# Safety_Loops.net
KiCad netlist of a schematic drawn in Altium Designer
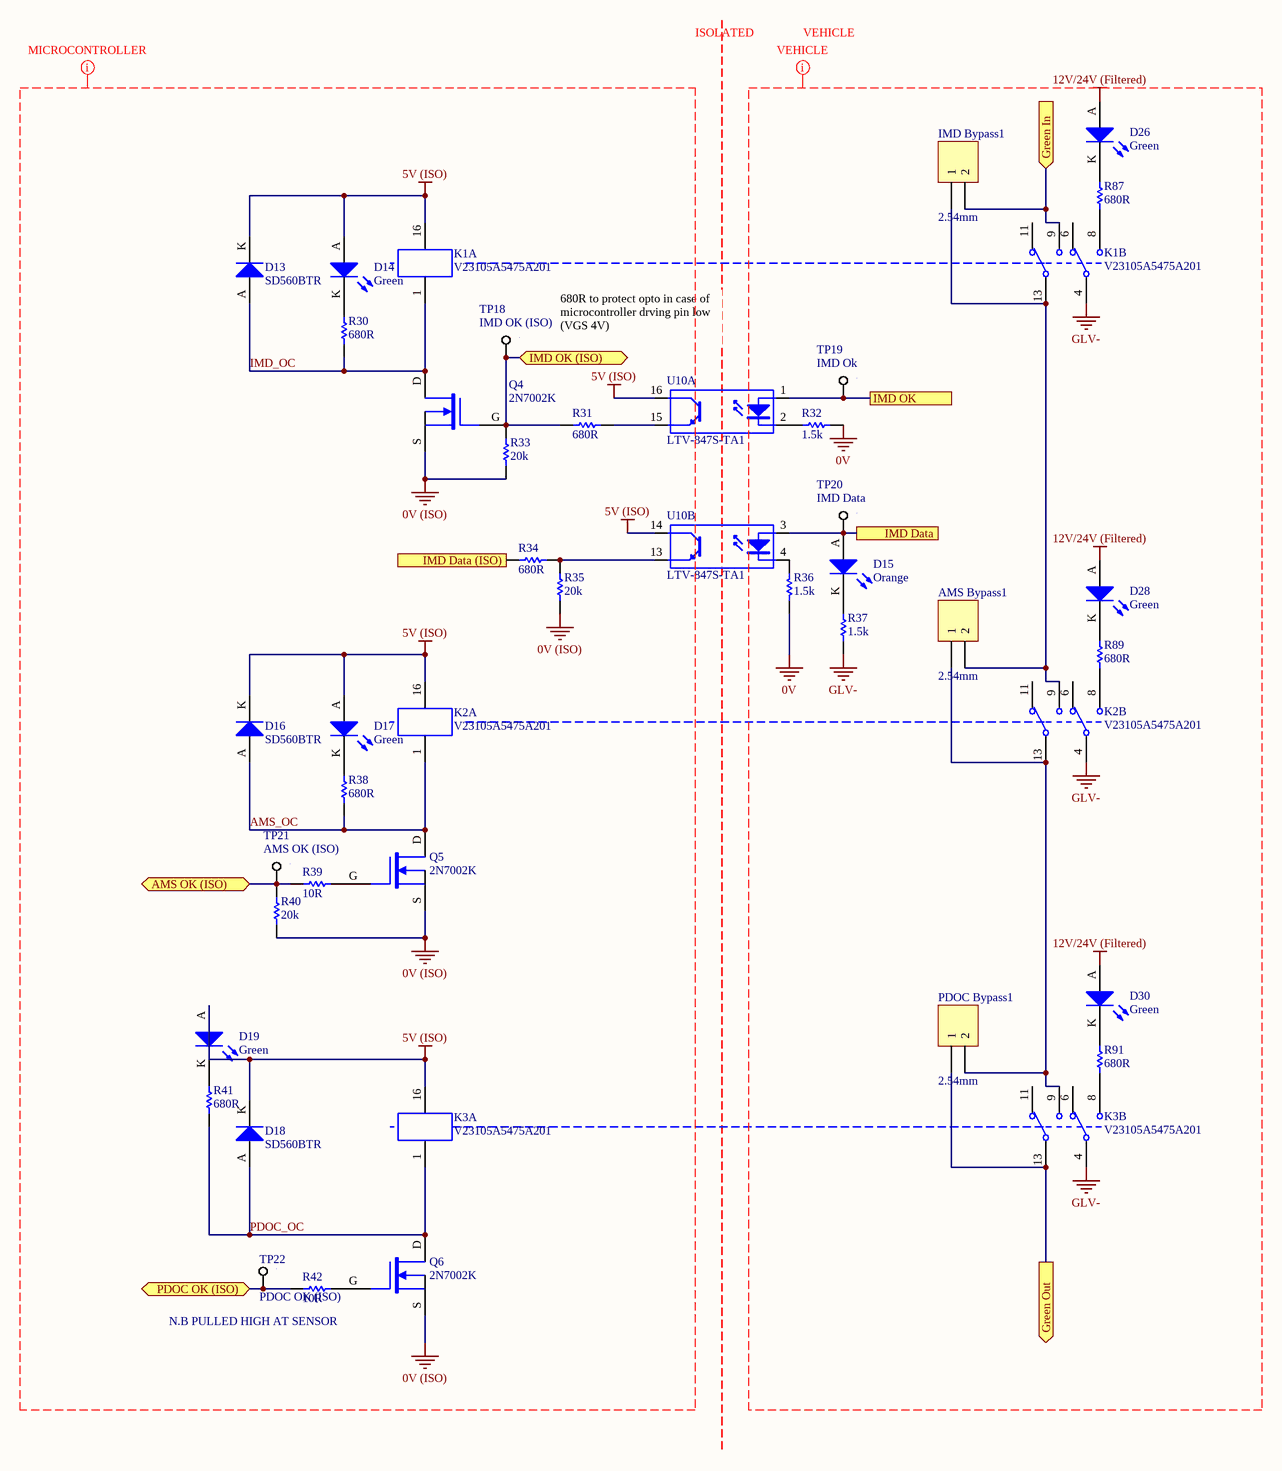
[diagram p0: Safety Loops.SchDoc]

(export (version "E")
  (design (tool "Eeschema 10.0.6"))
  (components
    (comp (ref "AMS Bypass1")
      (value "2.54mm")
      (footprint "TH 2.54mm Header 1x2")
      (fields (field (name "PART NUMBER") "TH 2.54mm Header 1x2") (field (name "CONTACT") "NA"))
      (libsource (lib "ts_20-standard-connectors") (part "Header 1x2"))
    )
    (comp (ref "D13")
      (value "SD560BTR")
      (footprint "SMB Diode")
      (description "1.2V_F 600V 5A SMB")
      (fields
        (field (name "MANUFACTURER") "SMC Diode Solutions")
        (field (name "DIGIKEY PART NUMBER") "1655-1530-2-ND")
      )
      (libsource (lib "ts_20-standard-library") (part "Diode"))
    )
    (comp (ref "D14")
      (value "Green")
      (footprint "0805 LED")
      (description "Green LED Indication - Discrete 1.75V 0805 (2012 Metric)")
      (fields (field (name "PART NUMBER") "SML-210FTT86") (field (name "MANUFACTURER") "ROHM Semiconductor"))
      (libsource (lib "ts_20-standard-library") (part "LED"))
    )
    (comp (ref "D15")
      (value "Orange")
      (footprint "0805 LED")
      (description "Orange LED Indication - Discrete 1.75V 0805 (2012 Metric)")
      (fields (field (name "PART NUMBER") "SML-211DTT86") (field (name "MANUFACTURER") "ROHM Semiconductor"))
      (libsource (lib "ts_20-standard-library") (part "LED"))
    )
    (comp (ref "D16")
      (value "SD560BTR")
      (footprint "SMB Diode")
      (description "1.2V_F 600V 5A SMB")
      (fields
        (field (name "MANUFACTURER") "SMC Diode Solutions")
        (field (name "DIGIKEY PART NUMBER") "1655-1530-2-ND")
      )
      (libsource (lib "ts_20-standard-library") (part "Diode"))
    )
    (comp (ref "D17")
      (value "Green")
      (footprint "0805 LED")
      (description "Green LED Indication - Discrete 1.75V 0805 (2012 Metric)")
      (fields (field (name "PART NUMBER") "SML-210FTT86") (field (name "MANUFACTURER") "ROHM Semiconductor"))
      (libsource (lib "ts_20-standard-library") (part "LED"))
    )
    (comp (ref "D18")
      (value "SD560BTR")
      (footprint "SMB Diode")
      (description "1.2V_F 600V 5A SMB")
      (fields
        (field (name "MANUFACTURER") "SMC Diode Solutions")
        (field (name "DIGIKEY PART NUMBER") "1655-1530-2-ND")
      )
      (libsource (lib "ts_20-standard-library") (part "Diode"))
    )
    (comp (ref "D19")
      (value "Green")
      (footprint "0805 LED")
      (description "Green LED Indication - Discrete 1.75V 0805 (2012 Metric)")
      (fields (field (name "PART NUMBER") "SML-210FTT86") (field (name "MANUFACTURER") "ROHM Semiconductor"))
      (libsource (lib "ts_20-standard-library") (part "LED"))
    )
    (comp (ref "D26")
      (value "Green")
      (footprint "0805 LED")
      (description "Green LED Indication - Discrete 1.75V 0805 (2012 Metric)")
      (fields (field (name "PART NUMBER") "SML-210FTT86") (field (name "MANUFACTURER") "ROHM Semiconductor"))
      (libsource (lib "ts_20-standard-library") (part "LED"))
    )
    (comp (ref "D28")
      (value "Green")
      (footprint "0805 LED")
      (description "Green LED Indication - Discrete 1.75V 0805 (2012 Metric)")
      (fields (field (name "PART NUMBER") "SML-210FTT86") (field (name "MANUFACTURER") "ROHM Semiconductor"))
      (libsource (lib "ts_20-standard-library") (part "LED"))
    )
    (comp (ref "D30")
      (value "Green")
      (footprint "0805 LED")
      (description "Green LED Indication - Discrete 1.75V 0805 (2012 Metric)")
      (fields (field (name "PART NUMBER") "SML-210FTT86") (field (name "MANUFACTURER") "ROHM Semiconductor"))
      (libsource (lib "ts_20-standard-library") (part "LED"))
    )
    (comp (ref "IMD Bypass1")
      (value "2.54mm")
      (footprint "TH 2.54mm Header 1x2")
      (fields (field (name "PART NUMBER") "TH 2.54mm Header 1x2") (field (name "CONTACT") "NA"))
      (libsource (lib "ts_20-standard-connectors") (part "Header 1x2"))
    )
    (comp (ref "K1")
      (value "V23105A5475A201")
      (footprint "TI 2-DIL")
      (description "5V DPDT Relay 3A 220VDC")
      (fields (field (name "MANUFACTURER") "Axicom") (field (name "DIGIKEY PART NUMBER") "PB383-ND"))
      (libsource (lib "") (part "V23105A5475A201_1"))
    )
    (comp (ref "K2")
      (value "V23105A5475A201")
      (footprint "TI 2-DIL")
      (description "5V DPDT Relay 3A 220VDC")
      (fields (field (name "MANUFACTURER") "Axicom") (field (name "DIGIKEY PART NUMBER") "PB383-ND"))
      (libsource (lib "") (part "V23105A5475A201_1"))
    )
    (comp (ref "K3")
      (value "V23105A5475A201")
      (footprint "TI 2-DIL")
      (description "5V DPDT Relay 3A 220VDC")
      (fields (field (name "MANUFACTURER") "Axicom") (field (name "DIGIKEY PART NUMBER") "PB383-ND"))
      (libsource (lib "") (part "V23105A5475A201_1"))
    )
    (comp (ref "PDOC Bypass1")
      (value "2.54mm")
      (footprint "TH 2.54mm Header 1x2")
      (fields (field (name "PART NUMBER") "TH 2.54mm Header 1x2") (field (name "CONTACT") "NA"))
      (libsource (lib "ts_20-standard-connectors") (part "Header 1x2"))
    )
    (comp (ref "Q4")
      (value "2N7002K")
      (footprint "ON SOT-23 MOSFET")
      (description "60V 380mA, NFET MOSTFET (Small Signal)")
      (fields
        (field (name "MANUFACTURER") "ON Semiconductor")
        (field (name "DIGIKEY PART NUMBER") "2N7002KCT-ND")
        (field (name "PUBLISHER") "Altium Limited")
      )
      (libsource (lib "ts_20-standard-library") (part "MOSFET-N"))
    )
    (comp (ref "Q5")
      (value "2N7002K")
      (footprint "ON SOT-23 MOSFET")
      (description "60V 380mA, NFET MOSTFET (Small Signal)")
      (fields
        (field (name "MANUFACTURER") "ON Semiconductor")
        (field (name "DIGIKEY PART NUMBER") "2N7002KCT-ND")
        (field (name "PUBLISHER") "Altium Limited")
      )
      (libsource (lib "ts_20-standard-library") (part "MOSFET-N"))
    )
    (comp (ref "Q6")
      (value "2N7002K")
      (footprint "ON SOT-23 MOSFET")
      (description "60V 380mA, NFET MOSTFET (Small Signal)")
      (fields
        (field (name "MANUFACTURER") "ON Semiconductor")
        (field (name "DIGIKEY PART NUMBER") "2N7002KCT-ND")
        (field (name "PUBLISHER") "Altium Limited")
      )
      (libsource (lib "ts_20-standard-library") (part "MOSFET-N"))
    )
    (comp (ref "R30")
      (value "680R")
      (footprint "0805")
      (fields
        (field (name "PART NUMBER") "RC0805FR07680RL")
        (field (name "MANUFACTURER") "YAGEO")
        (field (name "TOLERANCE") "0.01")
      )
      (libsource (lib "ts_20-standard-library") (part "Resistor"))
    )
    (comp (ref "R31")
      (value "680R")
      (footprint "0805")
      (fields
        (field (name "PART NUMBER") "RC0805FR07680RL")
        (field (name "MANUFACTURER") "YAGEO")
        (field (name "TOLERANCE") "0.01")
      )
      (libsource (lib "ts_20-standard-library") (part "Resistor"))
    )
    (comp (ref "R32")
      (value "1.5k")
      (footprint "0805")
      (fields
        (field (name "PART NUMBER") "RC0805FR071K5L")
        (field (name "MANUFACTURER") "YAGEO")
        (field (name "TOLERANCE") "0.01")
      )
      (libsource (lib "ts_20-standard-library") (part "Resistor"))
    )
    (comp (ref "R33")
      (value "20k")
      (footprint "0805")
      (fields
        (field (name "PART NUMBER") "RC0805FR0720KL")
        (field (name "MANUFACTURER") "YAGEO")
        (field (name "TOLERANCE") "0.01")
      )
      (libsource (lib "ts_20-standard-library") (part "Resistor"))
    )
    (comp (ref "R34")
      (value "680R")
      (footprint "0805")
      (fields
        (field (name "PART NUMBER") "RC0805FR07680RL")
        (field (name "MANUFACTURER") "YAGEO")
        (field (name "TOLERANCE") "0.01")
      )
      (libsource (lib "ts_20-standard-library") (part "Resistor"))
    )
    (comp (ref "R35")
      (value "20k")
      (footprint "0805")
      (fields
        (field (name "PART NUMBER") "RC0805FR0720KL")
        (field (name "MANUFACTURER") "YAGEO")
        (field (name "TOLERANCE") "0.01")
      )
      (libsource (lib "ts_20-standard-library") (part "Resistor"))
    )
    (comp (ref "R36")
      (value "1.5k")
      (footprint "0805")
      (fields
        (field (name "PART NUMBER") "RC0805FR071K5L")
        (field (name "MANUFACTURER") "YAGEO")
        (field (name "TOLERANCE") "0.01")
      )
      (libsource (lib "ts_20-standard-library") (part "Resistor"))
    )
    (comp (ref "R37")
      (value "1.5k")
      (footprint "0805")
      (fields
        (field (name "PART NUMBER") "RC0805FR071K5L")
        (field (name "MANUFACTURER") "YAGEO")
        (field (name "TOLERANCE") "0.01")
      )
      (libsource (lib "ts_20-standard-library") (part "Resistor"))
    )
    (comp (ref "R38")
      (value "680R")
      (footprint "0805")
      (fields
        (field (name "PART NUMBER") "RC0805FR07680RL")
        (field (name "MANUFACTURER") "YAGEO")
        (field (name "TOLERANCE") "0.01")
      )
      (libsource (lib "ts_20-standard-library") (part "Resistor"))
    )
    (comp (ref "R39")
      (value "10R")
      (footprint "0805")
      (fields
        (field (name "PART NUMBER") "RC0805FR0710RL")
        (field (name "MANUFACTURER") "YAGEO")
        (field (name "TOLERANCE") "0.01")
      )
      (libsource (lib "ts_20-standard-library") (part "Resistor"))
    )
    (comp (ref "R40")
      (value "20k")
      (footprint "0805")
      (fields
        (field (name "PART NUMBER") "RC0805FR0720KL")
        (field (name "MANUFACTURER") "YAGEO")
        (field (name "TOLERANCE") "0.01")
      )
      (libsource (lib "ts_20-standard-library") (part "Resistor"))
    )
    (comp (ref "R41")
      (value "680R")
      (footprint "0805")
      (fields
        (field (name "PART NUMBER") "RC0805FR07680RL")
        (field (name "MANUFACTURER") "YAGEO")
        (field (name "TOLERANCE") "0.01")
      )
      (libsource (lib "ts_20-standard-library") (part "Resistor"))
    )
    (comp (ref "R42")
      (value "10R")
      (footprint "0805")
      (fields
        (field (name "PART NUMBER") "RC0805FR0710RL")
        (field (name "MANUFACTURER") "YAGEO")
        (field (name "TOLERANCE") "0.01")
      )
      (libsource (lib "ts_20-standard-library") (part "Resistor"))
    )
    (comp (ref "R87")
      (value "680R")
      (footprint "0805")
      (fields
        (field (name "PART NUMBER") "RC0805FR07680RL")
        (field (name "MANUFACTURER") "YAGEO")
        (field (name "TOLERANCE") "0.01")
      )
      (libsource (lib "ts_20-standard-library") (part "Resistor"))
    )
    (comp (ref "R89")
      (value "680R")
      (footprint "0805")
      (fields
        (field (name "PART NUMBER") "RC0805FR07680RL")
        (field (name "MANUFACTURER") "YAGEO")
        (field (name "TOLERANCE") "0.01")
      )
      (libsource (lib "ts_20-standard-library") (part "Resistor"))
    )
    (comp (ref "R91")
      (value "680R")
      (footprint "0805")
      (fields
        (field (name "PART NUMBER") "RC0805FR07680RL")
        (field (name "MANUFACTURER") "YAGEO")
        (field (name "TOLERANCE") "0.01")
      )
      (libsource (lib "ts_20-standard-library") (part "Resistor"))
    )
    (comp (ref "TP18")
      (value "IMD OK (ISO)")
      (footprint "SMD Test Point 1mm")
      (fields (field (name "PART NUMBER") "SMD Test Point Small") (field (name "CONTACT") "NA"))
      (libsource (lib "ts_20-standard-connectors") (part "Test Point Small"))
    )
    (comp (ref "TP19")
      (value "IMD Ok")
      (footprint "SMD Test Point 1mm")
      (fields (field (name "PART NUMBER") "SMD Test Point Small") (field (name "CONTACT") "NA"))
      (libsource (lib "ts_20-standard-connectors") (part "Test Point Small"))
    )
    (comp (ref "TP20")
      (value "IMD Data")
      (footprint "SMD Test Point 1mm")
      (fields (field (name "PART NUMBER") "SMD Test Point Small") (field (name "CONTACT") "NA"))
      (libsource (lib "ts_20-standard-connectors") (part "Test Point Small"))
    )
    (comp (ref "TP21")
      (value "AMS OK (ISO)")
      (footprint "SMD Test Point 1mm")
      (fields (field (name "PART NUMBER") "SMD Test Point Small") (field (name "CONTACT") "NA"))
      (libsource (lib "ts_20-standard-connectors") (part "Test Point Small"))
    )
    (comp (ref "TP22")
      (value "PDOC OK (ISO)")
      (footprint "SMD Test Point 1mm")
      (fields (field (name "PART NUMBER") "SMD Test Point Small") (field (name "CONTACT") "NA"))
      (libsource (lib "ts_20-standard-connectors") (part "Test Point Small"))
    )
    (comp (ref "U10")
      (value "LTV-847S-TA1")
      (footprint "ON 16-SMD")
      (description "Optoisolator Transistor Output 5000Vrms 4 Channel 16-SMD")
      (fields
        (field (name "MANUFACTURER") "Lite-On Inc")
        (field (name "DIGIKEY PART NUMBER") "160-1371-5-ND")
      )
      (libsource (lib "ts_20-standard-library") (part "LTV-847S-TA1"))
    )
  )
  (nets
    (net (code "1") (name "/AMS OK (ISO)") (class "Default")
      (node (ref "R39") (pin "1") (pinfunction "1_1") (pintype "passive"))
      (node (ref "R40") (pin "2") (pinfunction "2_2") (pintype "passive"))
      (node (ref "TP21") (pin "1") (pinfunction "1_1") (pintype "passive"))
    )
    (net (code "2") (name "/AMS_OC") (class "Default")
      (node (ref "D16") (pin "A") (pinfunction "A_A") (pintype "passive"))
      (node (ref "K2") (pin "1") (pinfunction "1_1") (pintype "passive"))
      (node (ref "Q5") (pin "D") (pinfunction "D_D") (pintype "passive"))
      (node (ref "R38") (pin "1") (pinfunction "1_1") (pintype "passive"))
    )
    (net (code "3") (name "/Green In") (class "Default")
      (node (ref "IMD Bypass1") (pin "2") (pinfunction "2_2") (pintype "passive"))
      (node (ref "K1") (pin "9") (pinfunction "9_9") (pintype "passive"))
    )
    (net (code "4") (name "/Green Out") (class "Default")
      (node (ref "K3") (pin "13") (pinfunction "13_13") (pintype "passive"))
      (node (ref "PDOC Bypass1") (pin "1") (pinfunction "1_1") (pintype "passive"))
    )
    (net (code "5") (name "/IMD Data") (class "Default")
      (node (ref "D15") (pin "A") (pinfunction "A_A") (pintype "passive"))
      (node (ref "TP20") (pin "1") (pinfunction "1_1") (pintype "passive"))
      (node (ref "U10") (pin "3") (pinfunction "A_3") (pintype "passive"))
    )
    (net (code "6") (name "/IMD Data (ISO)") (class "Default")
      (node (ref "R34") (pin "1") (pinfunction "1_1") (pintype "passive"))
    )
    (net (code "7") (name "/IMD OK") (class "Default")
      (node (ref "TP19") (pin "1") (pinfunction "1_1") (pintype "passive"))
      (node (ref "U10") (pin "1") (pinfunction "A_1") (pintype "passive"))
    )
    (net (code "8") (name "/IMD OK (ISO)") (class "Default")
      (node (ref "Q4") (pin "G") (pinfunction "G_G") (pintype "passive"))
      (node (ref "R31") (pin "1") (pinfunction "1_1") (pintype "passive"))
      (node (ref "R33") (pin "2") (pinfunction "2_2") (pintype "passive"))
      (node (ref "TP18") (pin "1") (pinfunction "1_1") (pintype "passive"))
    )
    (net (code "9") (name "/IMD_OC") (class "Default")
      (node (ref "D13") (pin "A") (pinfunction "A_A") (pintype "passive"))
      (node (ref "K1") (pin "1") (pinfunction "1_1") (pintype "passive"))
      (node (ref "Q4") (pin "D") (pinfunction "D_D") (pintype "passive"))
      (node (ref "R30") (pin "1") (pinfunction "1_1") (pintype "passive"))
    )
    (net (code "10") (name "/PDOC OK (ISO)") (class "Default")
      (node (ref "R42") (pin "1") (pinfunction "1_1") (pintype "passive"))
      (node (ref "TP22") (pin "1") (pinfunction "1_1") (pintype "passive"))
    )
    (net (code "11") (name "/PDOC_OC") (class "Default")
      (node (ref "D18") (pin "A") (pinfunction "A_A") (pintype "passive"))
      (node (ref "K3") (pin "1") (pinfunction "1_1") (pintype "passive"))
      (node (ref "Q6") (pin "D") (pinfunction "D_D") (pintype "passive"))
      (node (ref "R41") (pin "1") (pinfunction "1_1") (pintype "passive"))
    )
    (net (code "12") (name "0V") (class "Default")
      (node (ref "R32") (pin "1") (pinfunction "1_1") (pintype "passive"))
      (node (ref "R36") (pin "2") (pinfunction "2_2") (pintype "passive"))
    )
    (net (code "13") (name "0V (ISO)") (class "Default")
      (node (ref "Q4") (pin "S") (pinfunction "S_S") (pintype "passive"))
      (node (ref "Q5") (pin "S") (pinfunction "S_S") (pintype "passive"))
      (node (ref "Q6") (pin "S") (pinfunction "S_S") (pintype "passive"))
      (node (ref "R33") (pin "1") (pinfunction "1_1") (pintype "passive"))
      (node (ref "R35") (pin "1") (pinfunction "1_1") (pintype "passive"))
      (node (ref "R40") (pin "1") (pinfunction "1_1") (pintype "passive"))
    )
    (net (code "14") (name "5V (ISO)") (class "Default")
      (node (ref "D13") (pin "K") (pinfunction "K_K") (pintype "passive"))
      (node (ref "D14") (pin "A") (pinfunction "A_A") (pintype "passive"))
      (node (ref "D16") (pin "K") (pinfunction "K_K") (pintype "passive"))
      (node (ref "D17") (pin "A") (pinfunction "A_A") (pintype "passive"))
      (node (ref "D18") (pin "K") (pinfunction "K_K") (pintype "passive"))
      (node (ref "D19") (pin "A") (pinfunction "A_A") (pintype "passive"))
      (node (ref "K1") (pin "16") (pinfunction "16_16") (pintype "passive"))
      (node (ref "K2") (pin "16") (pinfunction "16_16") (pintype "passive"))
      (node (ref "K3") (pin "16") (pinfunction "16_16") (pintype "passive"))
      (node (ref "U10") (pin "14") (pinfunction "C_14") (pintype "passive"))
      (node (ref "U10") (pin "16") (pinfunction "C_16") (pintype "passive"))
    )
    (net (code "15") (name "12V{slash}24V (Filtered)") (class "Default")
      (node (ref "D26") (pin "A") (pinfunction "A_A") (pintype "passive"))
      (node (ref "D28") (pin "A") (pinfunction "A_A") (pintype "passive"))
      (node (ref "D30") (pin "A") (pinfunction "A_A") (pintype "passive"))
    )
    (net (code "16") (name "GLV-") (class "Default")
      (node (ref "K1") (pin "4") (pinfunction "4_4") (pintype "passive"))
      (node (ref "K2") (pin "4") (pinfunction "4_4") (pintype "passive"))
      (node (ref "K3") (pin "4") (pinfunction "4_4") (pintype "passive"))
      (node (ref "R37") (pin "2") (pinfunction "2_2") (pintype "passive"))
    )
    (net (code "17") (name "Net-(AMS Bypass1-Pad1)") (class "Default")
      (node (ref "AMS Bypass1") (pin "1") (pinfunction "1_1") (pintype "passive"))
      (node (ref "K2") (pin "13") (pinfunction "13_13") (pintype "passive"))
      (node (ref "K3") (pin "9") (pinfunction "9_9") (pintype "passive"))
      (node (ref "PDOC Bypass1") (pin "2") (pinfunction "2_2") (pintype "passive"))
    )
    (net (code "18") (name "Net-(AMS Bypass1-Pad2)") (class "Default")
      (node (ref "AMS Bypass1") (pin "2") (pinfunction "2_2") (pintype "passive"))
      (node (ref "IMD Bypass1") (pin "1") (pinfunction "1_1") (pintype "passive"))
      (node (ref "K1") (pin "13") (pinfunction "13_13") (pintype "passive"))
      (node (ref "K2") (pin "9") (pinfunction "9_9") (pintype "passive"))
    )
    (net (code "19") (name "Net-(D14-PadK)") (class "Default")
      (node (ref "D14") (pin "K") (pinfunction "K_K") (pintype "passive"))
      (node (ref "R30") (pin "2") (pinfunction "2_2") (pintype "passive"))
    )
    (net (code "20") (name "Net-(D15-PadK)") (class "Default")
      (node (ref "D15") (pin "K") (pinfunction "K_K") (pintype "passive"))
      (node (ref "R37") (pin "1") (pinfunction "1_1") (pintype "passive"))
    )
    (net (code "21") (name "Net-(D17-PadK)") (class "Default")
      (node (ref "D17") (pin "K") (pinfunction "K_K") (pintype "passive"))
      (node (ref "R38") (pin "2") (pinfunction "2_2") (pintype "passive"))
    )
    (net (code "22") (name "Net-(D19-PadK)") (class "Default")
      (node (ref "D19") (pin "K") (pinfunction "K_K") (pintype "passive"))
      (node (ref "R41") (pin "2") (pinfunction "2_2") (pintype "passive"))
    )
    (net (code "23") (name "Net-(D26-PadK)") (class "Default")
      (node (ref "D26") (pin "K") (pinfunction "K_K") (pintype "passive"))
      (node (ref "R87") (pin "2") (pinfunction "2_2") (pintype "passive"))
    )
    (net (code "24") (name "Net-(D28-PadK)") (class "Default")
      (node (ref "D28") (pin "K") (pinfunction "K_K") (pintype "passive"))
      (node (ref "R89") (pin "2") (pinfunction "2_2") (pintype "passive"))
    )
    (net (code "25") (name "Net-(D30-PadK)") (class "Default")
      (node (ref "D30") (pin "K") (pinfunction "K_K") (pintype "passive"))
      (node (ref "R91") (pin "2") (pinfunction "2_2") (pintype "passive"))
    )
    (net (code "26") (name "Net-(K1-Pad8)") (class "Default")
      (node (ref "K1") (pin "8") (pinfunction "8_8") (pintype "passive"))
      (node (ref "R87") (pin "1") (pinfunction "1_1") (pintype "passive"))
    )
    (net (code "27") (name "Net-(K2-Pad8)") (class "Default")
      (node (ref "K2") (pin "8") (pinfunction "8_8") (pintype "passive"))
      (node (ref "R89") (pin "1") (pinfunction "1_1") (pintype "passive"))
    )
    (net (code "28") (name "Net-(K3-Pad8)") (class "Default")
      (node (ref "K3") (pin "8") (pinfunction "8_8") (pintype "passive"))
      (node (ref "R91") (pin "1") (pinfunction "1_1") (pintype "passive"))
    )
    (net (code "29") (name "Net-(Q5-PadG)") (class "Default")
      (node (ref "Q5") (pin "G") (pinfunction "G_G") (pintype "passive"))
      (node (ref "R39") (pin "2") (pinfunction "2_2") (pintype "passive"))
    )
    (net (code "30") (name "Net-(Q6-PadG)") (class "Default")
      (node (ref "Q6") (pin "G") (pinfunction "G_G") (pintype "passive"))
      (node (ref "R42") (pin "2") (pinfunction "2_2") (pintype "passive"))
    )
    (net (code "31") (name "Net-(U10A-E)") (class "Default")
      (node (ref "R31") (pin "2") (pinfunction "2_2") (pintype "passive"))
      (node (ref "U10") (pin "15") (pinfunction "E_15") (pintype "passive"))
    )
    (net (code "32") (name "Net-(U10A-K)") (class "Default")
      (node (ref "R32") (pin "2") (pinfunction "2_2") (pintype "passive"))
      (node (ref "U10") (pin "2") (pinfunction "K_2") (pintype "passive"))
    )
    (net (code "33") (name "Net-(U10B-E)") (class "Default")
      (node (ref "R34") (pin "2") (pinfunction "2_2") (pintype "passive"))
      (node (ref "R35") (pin "2") (pinfunction "2_2") (pintype "passive"))
      (node (ref "U10") (pin "13") (pinfunction "E_13") (pintype "passive"))
    )
    (net (code "34") (name "Net-(U10B-K)") (class "Default")
      (node (ref "R36") (pin "1") (pinfunction "1_1") (pintype "passive"))
      (node (ref "U10") (pin "4") (pinfunction "K_4") (pintype "passive"))
    )
    (net (code "35") (name "unconnected-(K1-Pad6)") (class "Default")
      (node (ref "K1") (pin "6") (pinfunction "6_6") (pintype "passive"))
    )
    (net (code "36") (name "unconnected-(K1-Pad11)") (class "Default")
      (node (ref "K1") (pin "11") (pinfunction "11_11") (pintype "passive"))
    )
    (net (code "37") (name "unconnected-(K2-Pad6)") (class "Default")
      (node (ref "K2") (pin "6") (pinfunction "6_6") (pintype "passive"))
    )
    (net (code "38") (name "unconnected-(K2-Pad11)") (class "Default")
      (node (ref "K2") (pin "11") (pinfunction "11_11") (pintype "passive"))
    )
    (net (code "39") (name "unconnected-(K3-Pad6)") (class "Default")
      (node (ref "K3") (pin "6") (pinfunction "6_6") (pintype "passive"))
    )
    (net (code "40") (name "unconnected-(K3-Pad11)") (class "Default")
      (node (ref "K3") (pin "11") (pinfunction "11_11") (pintype "passive"))
    )
  )
)
